# t10_adapter_board.net
KiCad netlist of a schematic drawn in EAGLE
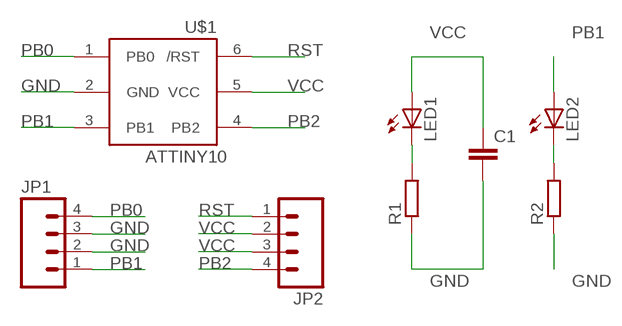
[diagram p0: schematic, sheet 1]

(export (version "E")
  (design (tool "Eeschema 10.0.6"))
  (components
    (comp (ref "C1")
      (value "C-EUC0805K")
      (footprint "eagle-import:C0805K")
      (libsource (lib "eagle-import") (part "C-EUC0805K"))
    )
    (comp (ref "JP1")
      (value "M04PTH")
      (footprint "eagle-import:1X04")
      (libsource (lib "eagle-import") (part "M04PTH"))
    )
    (comp (ref "JP2")
      (value "M04PTH")
      (footprint "eagle-import:1X04")
      (libsource (lib "eagle-import") (part "M04PTH"))
    )
    (comp (ref "LED1")
      (value "LEDCHIPLED_0805")
      (footprint "eagle-import:CHIPLED_0805")
      (libsource (lib "eagle-import") (part "LEDCHIPLED_0805"))
    )
    (comp (ref "LED2")
      (value "LEDCHIPLED_0805")
      (footprint "eagle-import:CHIPLED_0805")
      (libsource (lib "eagle-import") (part "LEDCHIPLED_0805"))
    )
    (comp (ref "R1")
      (value "R-EU_R0805")
      (footprint "eagle-import:R0805")
      (libsource (lib "eagle-import") (part "R-EU_R0805"))
    )
    (comp (ref "R2")
      (value "R-EU_R0805")
      (footprint "eagle-import:R0805")
      (libsource (lib "eagle-import") (part "R-EU_R0805"))
    )
    (comp (ref "U$1")
      (value "ATTINY10")
      (footprint "eagle-import:SOT23-6")
      (libsource (lib "eagle-import") (part "ATTINY10"))
    )
  )
  (nets
    (net (code "1") (name "/GND") (class "Default")
      (node (ref "C1") (pin "2") (pinfunction "2_2") (pintype "passive"))
      (node (ref "JP1") (pin "2") (pinfunction "2_2") (pintype "passive"))
      (node (ref "JP1") (pin "3") (pinfunction "3_3") (pintype "passive"))
      (node (ref "R1") (pin "1") (pinfunction "1_1") (pintype "passive"))
      (node (ref "R2") (pin "1") (pinfunction "1_1") (pintype "passive"))
      (node (ref "U$1") (pin "2") (pinfunction "GND_2") (pintype "power_in"))
    )
    (net (code "2") (name "/PB0") (class "Default")
      (node (ref "JP1") (pin "4") (pinfunction "4_4") (pintype "passive"))
      (node (ref "U$1") (pin "1") (pinfunction "PB0_1") (pintype "bidirectional"))
    )
    (net (code "3") (name "/PB1") (class "Default")
      (node (ref "JP1") (pin "1") (pinfunction "1_1") (pintype "passive"))
      (node (ref "LED2") (pin "A") (pinfunction "A_A") (pintype "passive"))
      (node (ref "U$1") (pin "3") (pinfunction "PB1_3") (pintype "bidirectional"))
    )
    (net (code "4") (name "/PB2") (class "Default")
      (node (ref "JP2") (pin "4") (pinfunction "4_4") (pintype "passive"))
      (node (ref "U$1") (pin "4") (pinfunction "PB2_4") (pintype "bidirectional"))
    )
    (net (code "5") (name "/RST") (class "Default")
      (node (ref "JP2") (pin "1") (pinfunction "1_1") (pintype "passive"))
      (node (ref "U$1") (pin "6") (pinfunction "/RST_6") (pintype "bidirectional"))
    )
    (net (code "6") (name "/VCC") (class "Default")
      (node (ref "C1") (pin "1") (pinfunction "1_1") (pintype "passive"))
      (node (ref "JP2") (pin "2") (pinfunction "2_2") (pintype "passive"))
      (node (ref "JP2") (pin "3") (pinfunction "3_3") (pintype "passive"))
      (node (ref "LED1") (pin "A") (pinfunction "A_A") (pintype "passive"))
      (node (ref "U$1") (pin "5") (pinfunction "VCC_5") (pintype "power_in"))
    )
    (net (code "7") (name "Net-(LED1-PadC)") (class "Default")
      (node (ref "LED1") (pin "C") (pinfunction "C_C") (pintype "passive"))
      (node (ref "R1") (pin "2") (pinfunction "2_2") (pintype "passive"))
    )
    (net (code "8") (name "Net-(LED2-PadC)") (class "Default")
      (node (ref "LED2") (pin "C") (pinfunction "C_C") (pintype "passive"))
      (node (ref "R2") (pin "2") (pinfunction "2_2") (pintype "passive"))
    )
  )
)
